# power_electronics8.net
KiCad netlist of a schematic drawn in EAGLE
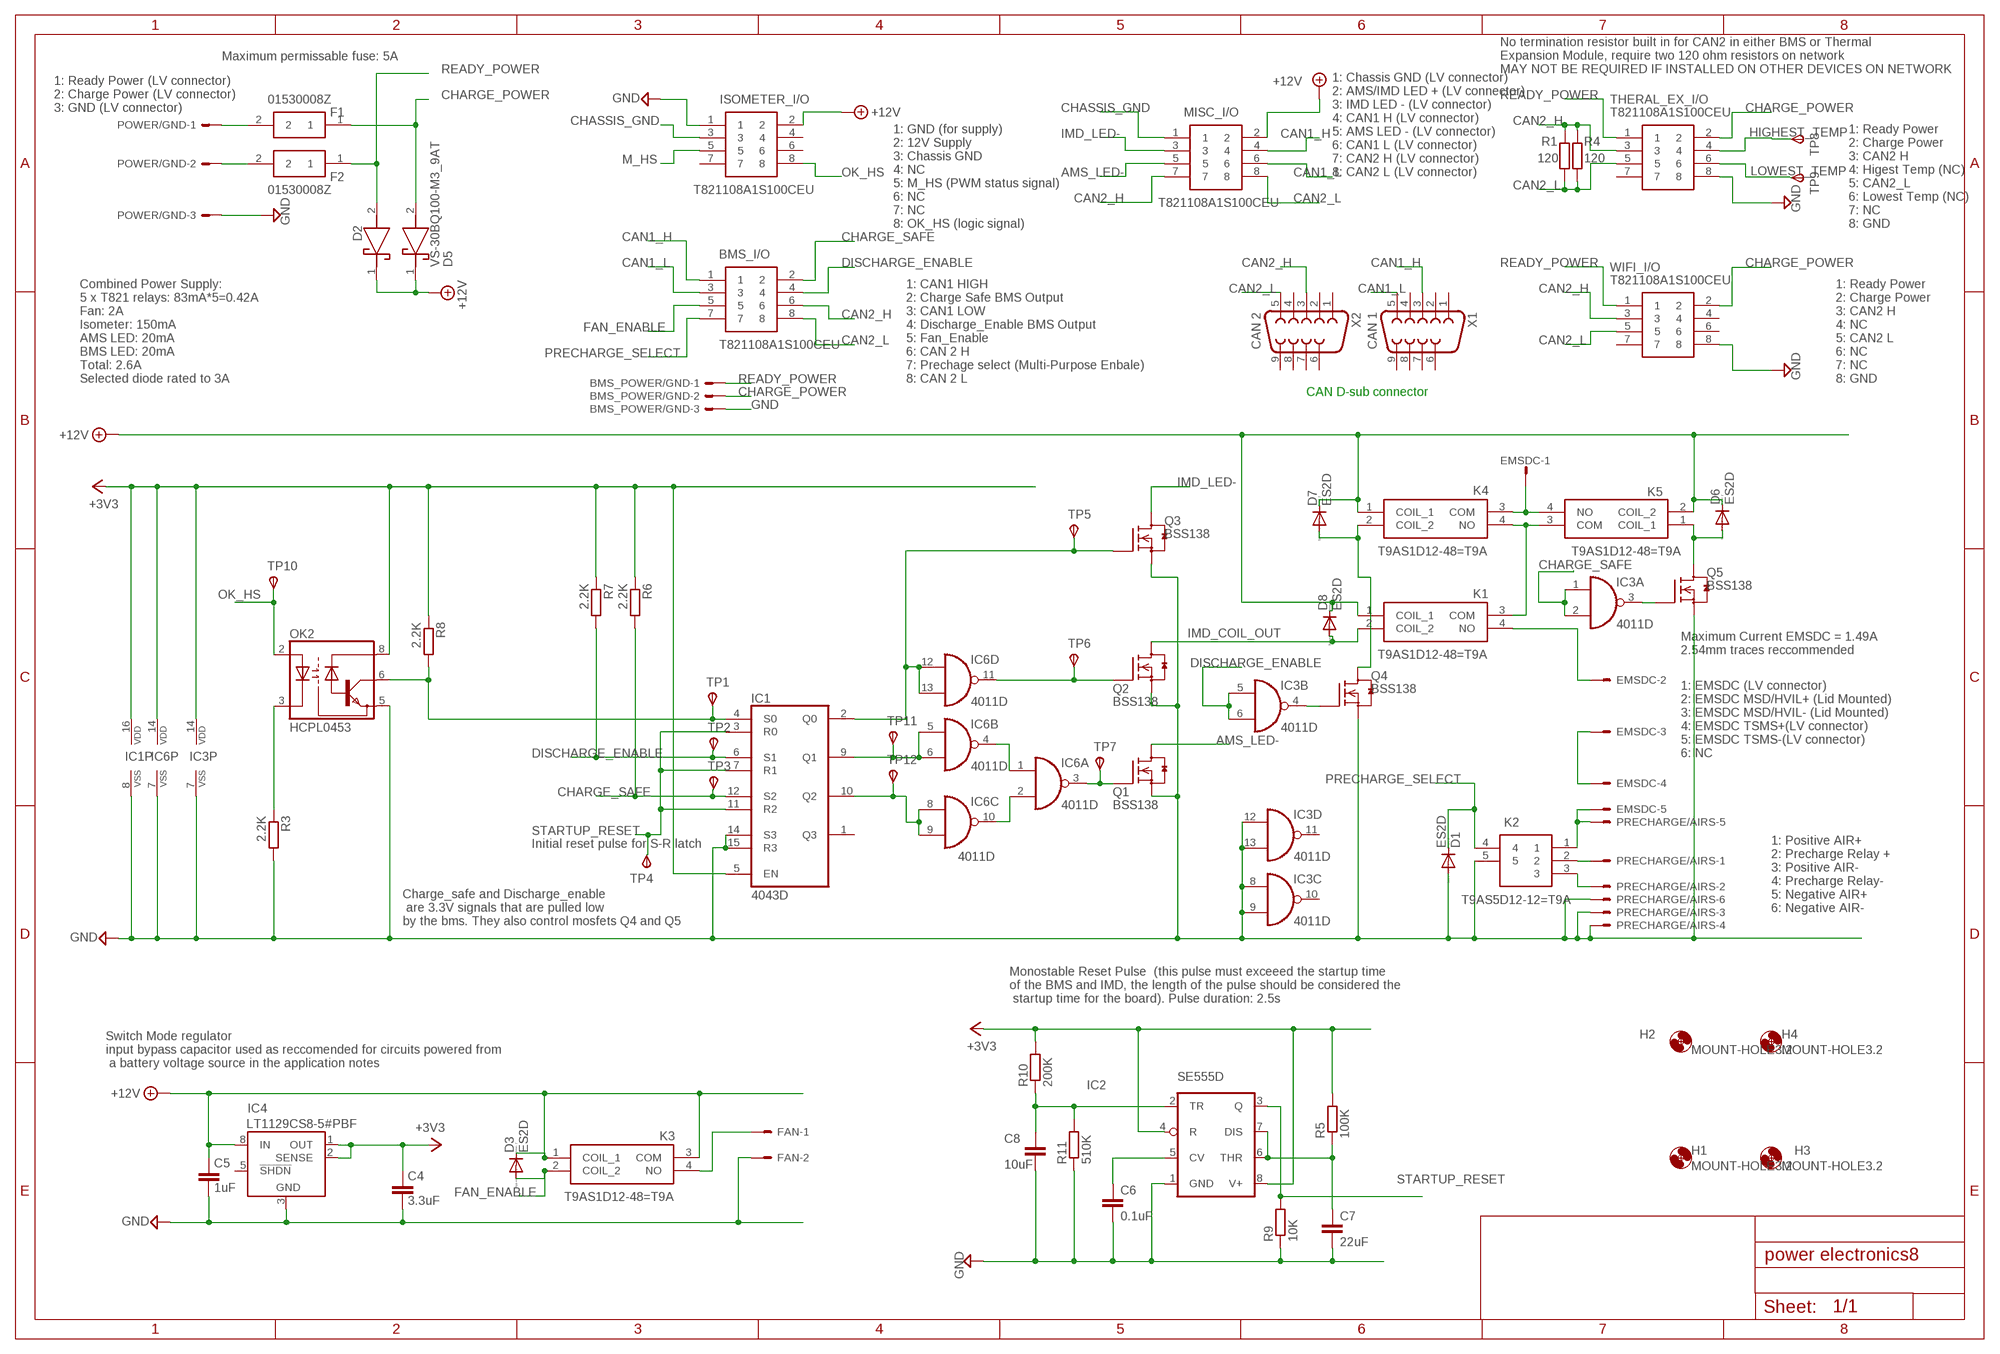
[diagram p0: schematic, sheet 1]

(export (version "E")
  (design (tool "Eeschema 10.0.6"))
  (components
    (comp (ref "BMS_I/O")
      (value "T821108A1S100CEU")
      (footprint "eagle-import:HDRV8W64P254_2X4_1778X895X915P")
      (fields (field (name "RS_PART_NUMBER") "8323569"))
      (libsource (lib "eagle-import") (part "T821108A1S100CEU"))
    )
    (comp (ref "BMS_POWER/GND")
      (value "KK-156-3")
      (footprint "eagle-import:KK-156-3")
      (fields (field (name "MF") "MOLEX"))
      (libsource (lib "eagle-import") (part "KK-156-3"))
    )
    (comp (ref "C4")
      (value "3.3uF")
      (footprint "eagle-import:C1206")
      (libsource (lib "eagle-import") (part "C-EUC1206"))
    )
    (comp (ref "C5")
      (value "1uF")
      (footprint "eagle-import:C1206")
      (libsource (lib "eagle-import") (part "C-EUC1206"))
    )
    (comp (ref "C6")
      (value "0.1uF")
      (footprint "eagle-import:C1206")
      (libsource (lib "eagle-import") (part "C-EUC1206"))
    )
    (comp (ref "C7")
      (value "22uF")
      (footprint "eagle-import:C1206")
      (libsource (lib "eagle-import") (part "C-EUC1206"))
    )
    (comp (ref "C8")
      (value "10uF")
      (footprint "eagle-import:C1206")
      (libsource (lib "eagle-import") (part "C-EUC1206"))
    )
    (comp (ref "D1")
      (value "ES2D")
      (footprint "eagle-import:SMB")
      (libsource (lib "eagle-import") (part "ES2D"))
    )
    (comp (ref "D2")
      (value "VS-30BQ100-M3_9AT")
      (footprint "eagle-import:DIOM7959X262N")
      (fields
        (field (name "MANUFACTURER_PART_NUMBER") "VS-30BQ100-M3/9AT")
        (field (name "MOUSER_PART_NUMBER") "78-VS-30BQ100-M39AT")
      )
      (libsource (lib "eagle-import") (part "VS-30BQ100-M3_9AT"))
    )
    (comp (ref "D3")
      (value "ES2D")
      (footprint "eagle-import:SMB")
      (libsource (lib "eagle-import") (part "ES2D"))
    )
    (comp (ref "D5")
      (value "VS-30BQ100-M3_9AT")
      (footprint "eagle-import:DIOM7959X262N")
      (fields
        (field (name "MANUFACTURER_PART_NUMBER") "VS-30BQ100-M3/9AT")
        (field (name "MOUSER_PART_NUMBER") "78-VS-30BQ100-M39AT")
      )
      (libsource (lib "eagle-import") (part "VS-30BQ100-M3_9AT"))
    )
    (comp (ref "D6")
      (value "ES2D")
      (footprint "eagle-import:SMB")
      (libsource (lib "eagle-import") (part "ES2D"))
    )
    (comp (ref "D7")
      (value "ES2D")
      (footprint "eagle-import:SMB")
      (libsource (lib "eagle-import") (part "ES2D"))
    )
    (comp (ref "D8")
      (value "ES2D")
      (footprint "eagle-import:SMB")
      (libsource (lib "eagle-import") (part "ES2D"))
    )
    (comp (ref "EMSDC")
      (value "KK-156-6")
      (footprint "eagle-import:KK-156-6")
      (fields (field (name "MF") "MOLEX"))
      (libsource (lib "eagle-import") (part "KK-156-6"))
    )
    (comp (ref "F1")
      (value "01530008Z")
      (footprint "eagle-import:01530008")
      (fields (field (name "RS_PART_NUMBER") "3607317"))
      (libsource (lib "eagle-import") (part "01530008Z"))
    )
    (comp (ref "F2")
      (value "01530008Z")
      (footprint "eagle-import:01530008")
      (fields (field (name "RS_PART_NUMBER") "3607317"))
      (libsource (lib "eagle-import") (part "01530008Z"))
    )
    (comp (ref "FAN")
      (value "KK-156-2")
      (footprint "eagle-import:KK-156-2")
      (fields (field (name "MF") "MOLEX"))
      (libsource (lib "eagle-import") (part "KK-156-2"))
    )
    (comp (ref "H1")
      (value "MOUNT-HOLE3.2")
      (footprint "eagle-import:3,2")
      (libsource (lib "eagle-import") (part "MOUNT-HOLE3.2"))
    )
    (comp (ref "H2")
      (value "MOUNT-HOLE3.2")
      (footprint "eagle-import:3,2")
      (libsource (lib "eagle-import") (part "MOUNT-HOLE3.2"))
    )
    (comp (ref "H3")
      (value "MOUNT-HOLE3.2")
      (footprint "eagle-import:3,2")
      (libsource (lib "eagle-import") (part "MOUNT-HOLE3.2"))
    )
    (comp (ref "H4")
      (value "MOUNT-HOLE3.2")
      (footprint "eagle-import:3,2")
      (libsource (lib "eagle-import") (part "MOUNT-HOLE3.2"))
    )
    (comp (ref "IC1")
      (value "4043D")
      (footprint "eagle-import:SO16")
      (libsource (lib "eagle-import") (part "4043D"))
    )
    (comp (ref "IC2")
      (value "SE555D")
      (footprint "eagle-import:SO08")
      (libsource (lib "eagle-import") (part "555DSE"))
    )
    (comp (ref "IC3")
      (value "4011D")
      (footprint "eagle-import:SO14")
      (libsource (lib "eagle-import") (part "4011D"))
    )
    (comp (ref "IC4")
      (value "LT1129CS8")
      (footprint "eagle-import:SOIC8")
      (fields (field (name "MPN") "LT1129CS8-5#PBF"))
      (libsource (lib "eagle-import") (part "LT1129CS8"))
    )
    (comp (ref "IC6")
      (value "4011D")
      (footprint "eagle-import:SO14")
      (libsource (lib "eagle-import") (part "4011D"))
    )
    (comp (ref "ISOMETER_I/O")
      (value "T821108A1S100CEU")
      (footprint "eagle-import:HDRV8W64P254_2X4_1778X895X915P")
      (fields (field (name "RS_PART_NUMBER") "8323569"))
      (libsource (lib "eagle-import") (part "T821108A1S100CEU"))
    )
    (comp (ref "K1")
      (value "T9AS1D12-48=T9A")
      (footprint "eagle-import:T9AS1D1248T9A")
      (fields (field (name "RS_PART_NUMBER") "6802534P"))
      (libsource (lib "eagle-import") (part "T9AS1D12-48=T9A"))
    )
    (comp (ref "K2")
      (value "T9AS5D12-12=T9A")
      (footprint "eagle-import:T9AS1D12")
      (fields (field (name "RS_PART_NUMBER") "6802528"))
      (libsource (lib "eagle-import") (part "T9AS5D12-12=T9A"))
    )
    (comp (ref "K3")
      (value "T9AS1D12-48=T9A")
      (footprint "eagle-import:T9AS1D1248T9A")
      (fields (field (name "RS_PART_NUMBER") "6802534P"))
      (libsource (lib "eagle-import") (part "T9AS1D12-48=T9A"))
    )
    (comp (ref "K4")
      (value "T9AS1D12-48=T9A")
      (footprint "eagle-import:T9AS1D1248T9A")
      (fields (field (name "RS_PART_NUMBER") "6802534P"))
      (libsource (lib "eagle-import") (part "T9AS1D12-48=T9A"))
    )
    (comp (ref "K5")
      (value "T9AS1D12-48=T9A")
      (footprint "eagle-import:T9AS1D1248T9A")
      (fields (field (name "RS_PART_NUMBER") "6802534P"))
      (libsource (lib "eagle-import") (part "T9AS1D12-48=T9A"))
    )
    (comp (ref "MISC_I/O")
      (value "T821108A1S100CEU")
      (footprint "eagle-import:HDRV8W64P254_2X4_1778X895X915P")
      (fields (field (name "RS_PART_NUMBER") "8323569"))
      (libsource (lib "eagle-import") (part "T821108A1S100CEU"))
    )
    (comp (ref "OK2")
      (value "HCPL0453")
      (footprint "eagle-import:SOIC08")
      (fields (field (name "MF") "AGILENT TECHNOLOGIES") (field (name "MPN") "HCPL-0453-000E"))
      (libsource (lib "eagle-import") (part "HCPL0453"))
    )
    (comp (ref "POWER/GND")
      (value "KK-156-3")
      (footprint "eagle-import:KK-156-3")
      (fields (field (name "MF") "MOLEX"))
      (libsource (lib "eagle-import") (part "KK-156-3"))
    )
    (comp (ref "PRECHARGE/AIRS")
      (value "KK-156-6")
      (footprint "eagle-import:KK-156-6")
      (fields (field (name "MF") "MOLEX"))
      (libsource (lib "eagle-import") (part "KK-156-6"))
    )
    (comp (ref "Q1")
      (value "BSS138")
      (footprint "eagle-import:SOT23")
      (libsource (lib "eagle-import") (part "BSS138"))
    )
    (comp (ref "Q2")
      (value "BSS138")
      (footprint "eagle-import:SOT23")
      (libsource (lib "eagle-import") (part "BSS138"))
    )
    (comp (ref "Q3")
      (value "BSS138")
      (footprint "eagle-import:SOT23")
      (libsource (lib "eagle-import") (part "BSS138"))
    )
    (comp (ref "Q4")
      (value "BSS138")
      (footprint "eagle-import:SOT23")
      (libsource (lib "eagle-import") (part "BSS138"))
    )
    (comp (ref "Q5")
      (value "BSS138")
      (footprint "eagle-import:SOT23")
      (libsource (lib "eagle-import") (part "BSS138"))
    )
    (comp (ref "R1")
      (value "120")
      (footprint "eagle-import:R1206")
      (libsource (lib "eagle-import") (part "R-EU_R1206"))
    )
    (comp (ref "R3")
      (value "2.2K")
      (footprint "eagle-import:R1206")
      (libsource (lib "eagle-import") (part "R-EU_R1206"))
    )
    (comp (ref "R4")
      (value "120")
      (footprint "eagle-import:R1206")
      (libsource (lib "eagle-import") (part "R-EU_R1206"))
    )
    (comp (ref "R5")
      (value "100K")
      (footprint "eagle-import:R1206")
      (libsource (lib "eagle-import") (part "R-EU_R1206"))
    )
    (comp (ref "R6")
      (value "2.2K")
      (footprint "eagle-import:R1206")
      (libsource (lib "eagle-import") (part "R-EU_R1206"))
    )
    (comp (ref "R7")
      (value "2.2K")
      (footprint "eagle-import:R1206")
      (libsource (lib "eagle-import") (part "R-EU_R1206"))
    )
    (comp (ref "R8")
      (value "2.2K")
      (footprint "eagle-import:R1206")
      (libsource (lib "eagle-import") (part "R-EU_R1206"))
    )
    (comp (ref "R9")
      (value "10K")
      (footprint "eagle-import:R1206")
      (libsource (lib "eagle-import") (part "R-EU_R1206"))
    )
    (comp (ref "R10")
      (value "200K")
      (footprint "eagle-import:R1206")
      (libsource (lib "eagle-import") (part "R-EU_R1206"))
    )
    (comp (ref "R11")
      (value "510K")
      (footprint "eagle-import:R1206")
      (libsource (lib "eagle-import") (part "R-EU_R1206"))
    )
    (comp (ref "THERAL_EX_I/O")
      (value "T821108A1S100CEU")
      (footprint "eagle-import:HDRV8W64P254_2X4_1778X895X915P")
      (fields (field (name "RS_PART_NUMBER") "8323569"))
      (libsource (lib "eagle-import") (part "T821108A1S100CEU"))
    )
    (comp (ref "TP1")
      (value "TPSTP11R")
      (footprint "eagle-import:TP11R")
      (libsource (lib "eagle-import") (part "TPSTP11R"))
    )
    (comp (ref "TP2")
      (value "TPSTP11R")
      (footprint "eagle-import:TP11R")
      (libsource (lib "eagle-import") (part "TPSTP11R"))
    )
    (comp (ref "TP3")
      (value "TPSTP11R")
      (footprint "eagle-import:TP11R")
      (libsource (lib "eagle-import") (part "TPSTP11R"))
    )
    (comp (ref "TP4")
      (value "TPSTP11R")
      (footprint "eagle-import:TP11R")
      (libsource (lib "eagle-import") (part "TPSTP11R"))
    )
    (comp (ref "TP5")
      (value "TPSTP11R")
      (footprint "eagle-import:TP11R")
      (libsource (lib "eagle-import") (part "TPSTP11R"))
    )
    (comp (ref "TP6")
      (value "TPSTP11R")
      (footprint "eagle-import:TP11R")
      (libsource (lib "eagle-import") (part "TPSTP11R"))
    )
    (comp (ref "TP7")
      (value "TPSTP11R")
      (footprint "eagle-import:TP11R")
      (libsource (lib "eagle-import") (part "TPSTP11R"))
    )
    (comp (ref "TP8")
      (value "TPSTP11R")
      (footprint "eagle-import:TP11R")
      (libsource (lib "eagle-import") (part "TPSTP11R"))
    )
    (comp (ref "TP9")
      (value "TPSTP11R")
      (footprint "eagle-import:TP11R")
      (libsource (lib "eagle-import") (part "TPSTP11R"))
    )
    (comp (ref "TP10")
      (value "TPSTP11R")
      (footprint "eagle-import:TP11R")
      (libsource (lib "eagle-import") (part "TPSTP11R"))
    )
    (comp (ref "TP11")
      (value "TPSTP11R")
      (footprint "eagle-import:TP11R")
      (libsource (lib "eagle-import") (part "TPSTP11R"))
    )
    (comp (ref "TP12")
      (value "TPSTP11R")
      (footprint "eagle-import:TP11R")
      (libsource (lib "eagle-import") (part "TPSTP11R"))
    )
    (comp (ref "WIFI_I/O")
      (value "T821108A1S100CEU")
      (footprint "eagle-import:HDRV8W64P254_2X4_1778X895X915P")
      (fields (field (name "RS_PART_NUMBER") "8323569"))
      (libsource (lib "eagle-import") (part "T821108A1S100CEU"))
    )
    (comp (ref "X1")
      (value "CAN 1")
      (footprint "eagle-import:F09V")
      (libsource (lib "eagle-import") (part "F09V"))
    )
    (comp (ref "X2")
      (value "CAN 2")
      (footprint "eagle-import:F09V")
      (libsource (lib "eagle-import") (part "F09V"))
    )
  )
  (nets
    (net (code "1") (name "+3V3") (class "Default")
      (node (ref "C4") (pin "1") (pinfunction "1_1") (pintype "passive"))
      (node (ref "IC1") (pin "16") (pinfunction "VDD_16") (pintype "power_in"))
      (node (ref "IC1") (pin "5") (pinfunction "EN_5") (pintype "input"))
      (node (ref "IC2") (pin "4") (pinfunction "R_4") (pintype "input"))
      (node (ref "IC2") (pin "8") (pinfunction "V+_8") (pintype "power_in"))
      (node (ref "IC3") (pin "14") (pinfunction "VDD_14") (pintype "power_in"))
      (node (ref "IC4") (pin "1") (pinfunction "OUT_1") (pintype "output"))
      (node (ref "IC4") (pin "2") (pinfunction "SENSE_2") (pintype "input"))
      (node (ref "IC6") (pin "14") (pinfunction "VDD_14") (pintype "power_in"))
      (node (ref "OK2") (pin "8") (pinfunction "VCC_8") (pintype "passive"))
      (node (ref "R10") (pin "2") (pinfunction "2_2") (pintype "passive"))
      (node (ref "R5") (pin "2") (pinfunction "2_2") (pintype "passive"))
      (node (ref "R6") (pin "1") (pinfunction "1_1") (pintype "passive"))
      (node (ref "R7") (pin "1") (pinfunction "1_1") (pintype "passive"))
      (node (ref "R8") (pin "1") (pinfunction "1_1") (pintype "passive"))
    )
    (net (code "2") (name "+12V") (class "Default")
      (node (ref "C5") (pin "1") (pinfunction "1_1") (pintype "passive"))
      (node (ref "D2") (pin "1") (pinfunction "K_1") (pintype "bidirectional"))
      (node (ref "D3") (pin "C") (pinfunction "C_C") (pintype "passive"))
      (node (ref "D5") (pin "1") (pinfunction "K_1") (pintype "bidirectional"))
      (node (ref "D6") (pin "C") (pinfunction "C_C") (pintype "passive"))
      (node (ref "D7") (pin "C") (pinfunction "C_C") (pintype "passive"))
      (node (ref "D8") (pin "C") (pinfunction "C_C") (pintype "passive"))
      (node (ref "IC4") (pin "8") (pinfunction "IN_8") (pintype "input"))
      (node (ref "ISOMETER_I/O") (pin "2") (pinfunction "2_2") (pintype "bidirectional"))
      (node (ref "K1") (pin "1") (pinfunction "COIL_1_1") (pintype "bidirectional"))
      (node (ref "K3") (pin "1") (pinfunction "COIL_1_1") (pintype "bidirectional"))
      (node (ref "K3") (pin "3") (pinfunction "COM_3") (pintype "bidirectional"))
      (node (ref "K4") (pin "1") (pinfunction "COIL_1_1") (pintype "bidirectional"))
      (node (ref "K5") (pin "2") (pinfunction "COIL_2_2") (pintype "bidirectional"))
      (node (ref "MISC_I/O") (pin "2") (pinfunction "2_2") (pintype "bidirectional"))
    )
    (net (code "3") (name "/AMS_LED-") (class "Default")
      (node (ref "MISC_I/O") (pin "5") (pinfunction "5_5") (pintype "bidirectional"))
      (node (ref "Q1") (pin "3") (pinfunction "D_3") (pintype "passive"))
    )
    (net (code "4") (name "/CAN1_H") (class "Default")
      (node (ref "BMS_I/O") (pin "1") (pinfunction "1_1") (pintype "bidirectional"))
      (node (ref "MISC_I/O") (pin "4") (pinfunction "4_4") (pintype "bidirectional"))
      (node (ref "X1") (pin "3") (pinfunction "3_3") (pintype "passive"))
    )
    (net (code "5") (name "/CAN1_L") (class "Default")
      (node (ref "BMS_I/O") (pin "3") (pinfunction "3_3") (pintype "bidirectional"))
      (node (ref "MISC_I/O") (pin "6") (pinfunction "6_6") (pintype "bidirectional"))
      (node (ref "X1") (pin "5") (pinfunction "5_5") (pintype "passive"))
    )
    (net (code "6") (name "/CAN2_H") (class "Default")
      (node (ref "BMS_I/O") (pin "6") (pinfunction "6_6") (pintype "bidirectional"))
      (node (ref "MISC_I/O") (pin "7") (pinfunction "7_7") (pintype "bidirectional"))
      (node (ref "R1") (pin "1") (pinfunction "1_1") (pintype "passive"))
      (node (ref "R4") (pin "1") (pinfunction "1_1") (pintype "passive"))
      (node (ref "THERAL_EX_I/O") (pin "3") (pinfunction "3_3") (pintype "bidirectional"))
      (node (ref "WIFI_I/O") (pin "3") (pinfunction "3_3") (pintype "bidirectional"))
      (node (ref "X2") (pin "3") (pinfunction "3_3") (pintype "passive"))
    )
    (net (code "7") (name "/CAN2_L") (class "Default")
      (node (ref "BMS_I/O") (pin "8") (pinfunction "8_8") (pintype "bidirectional"))
      (node (ref "MISC_I/O") (pin "8") (pinfunction "8_8") (pintype "bidirectional"))
      (node (ref "R1") (pin "2") (pinfunction "2_2") (pintype "passive"))
      (node (ref "R4") (pin "2") (pinfunction "2_2") (pintype "passive"))
      (node (ref "THERAL_EX_I/O") (pin "5") (pinfunction "5_5") (pintype "bidirectional"))
      (node (ref "WIFI_I/O") (pin "5") (pinfunction "5_5") (pintype "bidirectional"))
      (node (ref "X2") (pin "5") (pinfunction "5_5") (pintype "passive"))
    )
    (net (code "8") (name "/CHARGE_POWER") (class "Default")
      (node (ref "BMS_POWER/GND") (pin "2") (pinfunction "S_2") (pintype "passive"))
      (node (ref "D5") (pin "2") (pinfunction "A_2") (pintype "bidirectional"))
      (node (ref "F1") (pin "1") (pinfunction "1_1") (pintype "bidirectional"))
      (node (ref "THERAL_EX_I/O") (pin "2") (pinfunction "2_2") (pintype "bidirectional"))
      (node (ref "WIFI_I/O") (pin "2") (pinfunction "2_2") (pintype "bidirectional"))
    )
    (net (code "9") (name "/CHARGE_SAFE") (class "Default")
      (node (ref "BMS_I/O") (pin "2") (pinfunction "2_2") (pintype "bidirectional"))
      (node (ref "IC1") (pin "12") (pinfunction "S2_12") (pintype "input"))
      (node (ref "IC3") (pin "1") (pinfunction "I0_1") (pintype "input"))
      (node (ref "IC3") (pin "2") (pinfunction "I1_2") (pintype "input"))
      (node (ref "R6") (pin "2") (pinfunction "2_2") (pintype "passive"))
      (node (ref "TP3") (pin "TP") (pinfunction "PP_TP") (pintype "input"))
    )
    (net (code "10") (name "/CHASSIS_GND") (class "Default")
      (node (ref "ISOMETER_I/O") (pin "3") (pinfunction "3_3") (pintype "bidirectional"))
      (node (ref "MISC_I/O") (pin "1") (pinfunction "1_1") (pintype "bidirectional"))
    )
    (net (code "11") (name "/DISCHARGE_ENABLE") (class "Default")
      (node (ref "BMS_I/O") (pin "4") (pinfunction "4_4") (pintype "bidirectional"))
      (node (ref "IC1") (pin "6") (pinfunction "S1_6") (pintype "input"))
      (node (ref "IC3") (pin "5") (pinfunction "I0_5") (pintype "input"))
      (node (ref "IC3") (pin "6") (pinfunction "I1_6") (pintype "input"))
      (node (ref "R7") (pin "2") (pinfunction "2_2") (pintype "passive"))
      (node (ref "TP2") (pin "TP") (pinfunction "PP_TP") (pintype "input"))
    )
    (net (code "12") (name "/FAN_ENABLE") (class "Default")
      (node (ref "BMS_I/O") (pin "5") (pinfunction "5_5") (pintype "bidirectional"))
      (node (ref "D3") (pin "A") (pinfunction "A_A") (pintype "passive"))
      (node (ref "K3") (pin "2") (pinfunction "COIL_2_2") (pintype "bidirectional"))
    )
    (net (code "13") (name "/HIGHEST_TEMP") (class "Default")
      (node (ref "THERAL_EX_I/O") (pin "4") (pinfunction "4_4") (pintype "bidirectional"))
      (node (ref "TP8") (pin "TP") (pinfunction "PP_TP") (pintype "input"))
    )
    (net (code "14") (name "/IMD_COIL_OUT") (class "Default")
      (node (ref "D8") (pin "A") (pinfunction "A_A") (pintype "passive"))
      (node (ref "K1") (pin "2") (pinfunction "COIL_2_2") (pintype "bidirectional"))
      (node (ref "Q2") (pin "3") (pinfunction "D_3") (pintype "passive"))
    )
    (net (code "15") (name "/IMD_LED-") (class "Default")
      (node (ref "MISC_I/O") (pin "3") (pinfunction "3_3") (pintype "bidirectional"))
      (node (ref "Q3") (pin "3") (pinfunction "D_3") (pintype "passive"))
    )
    (net (code "16") (name "/LOWEST_TEMP") (class "Default")
      (node (ref "THERAL_EX_I/O") (pin "6") (pinfunction "6_6") (pintype "bidirectional"))
      (node (ref "TP9") (pin "TP") (pinfunction "PP_TP") (pintype "input"))
    )
    (net (code "17") (name "/M_HS") (class "Default")
      (node (ref "ISOMETER_I/O") (pin "5") (pinfunction "5_5") (pintype "bidirectional"))
    )
    (net (code "18") (name "/OK_HS") (class "Default")
      (node (ref "ISOMETER_I/O") (pin "8") (pinfunction "8_8") (pintype "bidirectional"))
      (node (ref "OK2") (pin "2") (pinfunction "A_2") (pintype "passive"))
      (node (ref "TP10") (pin "TP") (pinfunction "PP_TP") (pintype "input"))
    )
    (net (code "19") (name "/PRECHARGE_SELECT") (class "Default")
      (node (ref "BMS_I/O") (pin "7") (pinfunction "7_7") (pintype "bidirectional"))
      (node (ref "D1") (pin "C") (pinfunction "C_C") (pintype "passive"))
      (node (ref "K2") (pin "4") (pinfunction "4_4") (pintype "bidirectional"))
    )
    (net (code "20") (name "/READY_POWER") (class "Default")
      (node (ref "BMS_POWER/GND") (pin "1") (pinfunction "S_1") (pintype "passive"))
      (node (ref "D2") (pin "2") (pinfunction "A_2") (pintype "bidirectional"))
      (node (ref "F2") (pin "1") (pinfunction "1_1") (pintype "bidirectional"))
      (node (ref "THERAL_EX_I/O") (pin "1") (pinfunction "1_1") (pintype "bidirectional"))
      (node (ref "WIFI_I/O") (pin "1") (pinfunction "1_1") (pintype "bidirectional"))
    )
    (net (code "21") (name "/STARTUP_RESET") (class "Default")
      (node (ref "IC1") (pin "11") (pinfunction "R2_11") (pintype "input"))
      (node (ref "IC1") (pin "3") (pinfunction "R0_3") (pintype "input"))
      (node (ref "IC1") (pin "7") (pinfunction "R1_7") (pintype "input"))
      (node (ref "IC2") (pin "3") (pinfunction "Q_3") (pintype "output"))
      (node (ref "R9") (pin "2") (pinfunction "2_2") (pintype "passive"))
      (node (ref "TP4") (pin "TP") (pinfunction "PP_TP") (pintype "input"))
    )
    (net (code "22") (name "GND") (class "Default")
      (node (ref "BMS_POWER/GND") (pin "3") (pinfunction "S_3") (pintype "passive"))
      (node (ref "C4") (pin "2") (pinfunction "2_2") (pintype "passive"))
      (node (ref "C5") (pin "2") (pinfunction "2_2") (pintype "passive"))
      (node (ref "C6") (pin "2") (pinfunction "2_2") (pintype "passive"))
      (node (ref "C7") (pin "2") (pinfunction "2_2") (pintype "passive"))
      (node (ref "C8") (pin "2") (pinfunction "2_2") (pintype "passive"))
      (node (ref "D1") (pin "A") (pinfunction "A_A") (pintype "passive"))
      (node (ref "FAN") (pin "2") (pinfunction "S_2") (pintype "passive"))
      (node (ref "IC1") (pin "14") (pinfunction "S3_14") (pintype "input"))
      (node (ref "IC1") (pin "15") (pinfunction "R3_15") (pintype "input"))
      (node (ref "IC1") (pin "8") (pinfunction "VSS_8") (pintype "power_in"))
      (node (ref "IC2") (pin "1") (pinfunction "GND_1") (pintype "power_in"))
      (node (ref "IC3") (pin "12") (pinfunction "I0_12") (pintype "input"))
      (node (ref "IC3") (pin "13") (pinfunction "I1_13") (pintype "input"))
      (node (ref "IC3") (pin "7") (pinfunction "VSS_7") (pintype "power_in"))
      (node (ref "IC3") (pin "8") (pinfunction "I0_8") (pintype "input"))
      (node (ref "IC3") (pin "9") (pinfunction "I1_9") (pintype "input"))
      (node (ref "IC4") (pin "3") (pinfunction "GND_3") (pintype "power_in"))
      (node (ref "IC6") (pin "7") (pinfunction "VSS_7") (pintype "power_in"))
      (node (ref "ISOMETER_I/O") (pin "1") (pinfunction "1_1") (pintype "bidirectional"))
      (node (ref "K2") (pin "5") (pinfunction "5_5") (pintype "bidirectional"))
      (node (ref "OK2") (pin "5") (pinfunction "GND_5") (pintype "passive"))
      (node (ref "POWER/GND") (pin "3") (pinfunction "S_3") (pintype "passive"))
      (node (ref "PRECHARGE/AIRS") (pin "3") (pinfunction "S_3") (pintype "passive"))
      (node (ref "PRECHARGE/AIRS") (pin "4") (pinfunction "S_4") (pintype "passive"))
      (node (ref "PRECHARGE/AIRS") (pin "6") (pinfunction "S_6") (pintype "passive"))
      (node (ref "Q1") (pin "2") (pinfunction "S_2") (pintype "passive"))
      (node (ref "Q2") (pin "2") (pinfunction "S_2") (pintype "passive"))
      (node (ref "Q3") (pin "2") (pinfunction "S_2") (pintype "passive"))
      (node (ref "Q4") (pin "2") (pinfunction "S_2") (pintype "passive"))
      (node (ref "Q5") (pin "2") (pinfunction "S_2") (pintype "passive"))
      (node (ref "R11") (pin "1") (pinfunction "1_1") (pintype "passive"))
      (node (ref "R3") (pin "2") (pinfunction "2_2") (pintype "passive"))
      (node (ref "R9") (pin "1") (pinfunction "1_1") (pintype "passive"))
      (node (ref "THERAL_EX_I/O") (pin "8") (pinfunction "8_8") (pintype "bidirectional"))
      (node (ref "WIFI_I/O") (pin "8") (pinfunction "8_8") (pintype "bidirectional"))
    )
    (net (code "23") (name "Net-(EMSDCA-S)") (class "Default")
      (node (ref "EMSDC") (pin "1") (pinfunction "S_1") (pintype "passive"))
      (node (ref "K4") (pin "3") (pinfunction "COM_3") (pintype "bidirectional"))
      (node (ref "K5") (pin "4") (pinfunction "NO_4") (pintype "bidirectional"))
    )
    (net (code "24") (name "Net-(EMSDCB-S)") (class "Default")
      (node (ref "EMSDC") (pin "2") (pinfunction "S_2") (pintype "passive"))
      (node (ref "K1") (pin "4") (pinfunction "NO_4") (pintype "bidirectional"))
    )
    (net (code "25") (name "Net-(EMSDCC-S)") (class "Default")
      (node (ref "EMSDC") (pin "3") (pinfunction "S_3") (pintype "passive"))
      (node (ref "EMSDC") (pin "4") (pinfunction "S_4") (pintype "passive"))
    )
    (net (code "26") (name "Net-(EMSDCE-S)") (class "Default")
      (node (ref "EMSDC") (pin "5") (pinfunction "S_5") (pintype "passive"))
      (node (ref "K2") (pin "1") (pinfunction "1_1") (pintype "bidirectional"))
      (node (ref "PRECHARGE/AIRS") (pin "5") (pinfunction "S_5") (pintype "passive"))
    )
    (net (code "27") (name "Net-(FANA-S)") (class "Default")
      (node (ref "FAN") (pin "1") (pinfunction "S_1") (pintype "passive"))
      (node (ref "K3") (pin "4") (pinfunction "NO_4") (pintype "bidirectional"))
    )
    (net (code "28") (name "Net-(IC1A-Q0)") (class "Default")
      (node (ref "IC1") (pin "2") (pinfunction "Q0_2") (pintype "output"))
      (node (ref "IC6") (pin "12") (pinfunction "I0_12") (pintype "input"))
      (node (ref "IC6") (pin "13") (pinfunction "I1_13") (pintype "input"))
      (node (ref "Q3") (pin "1") (pinfunction "G_1") (pintype "passive"))
      (node (ref "TP5") (pin "TP") (pinfunction "PP_TP") (pintype "input"))
    )
    (net (code "29") (name "Net-(IC1A-Q1)") (class "Default")
      (node (ref "IC1") (pin "9") (pinfunction "Q1_9") (pintype "output"))
      (node (ref "IC6") (pin "5") (pinfunction "I0_5") (pintype "input"))
      (node (ref "IC6") (pin "6") (pinfunction "I1_6") (pintype "input"))
      (node (ref "TP11") (pin "TP") (pinfunction "PP_TP") (pintype "input"))
    )
    (net (code "30") (name "Net-(IC1A-Q2)") (class "Default")
      (node (ref "IC1") (pin "10") (pinfunction "Q2_10") (pintype "output"))
      (node (ref "IC6") (pin "8") (pinfunction "I0_8") (pintype "input"))
      (node (ref "IC6") (pin "9") (pinfunction "I1_9") (pintype "input"))
      (node (ref "TP12") (pin "TP") (pinfunction "PP_TP") (pintype "input"))
    )
    (net (code "31") (name "Net-(IC1A-S0)") (class "Default")
      (node (ref "IC1") (pin "4") (pinfunction "S0_4") (pintype "input"))
      (node (ref "OK2") (pin "6") (pinfunction "VO_6") (pintype "passive"))
      (node (ref "R8") (pin "2") (pinfunction "2_2") (pintype "passive"))
      (node (ref "TP1") (pin "TP") (pinfunction "PP_TP") (pintype "input"))
    )
    (net (code "32") (name "Net-(IC2-CV)") (class "Default")
      (node (ref "C6") (pin "1") (pinfunction "1_1") (pintype "passive"))
      (node (ref "IC2") (pin "5") (pinfunction "CV_5") (pintype "input"))
    )
    (net (code "33") (name "Net-(IC2-DIS)") (class "Default")
      (node (ref "C7") (pin "1") (pinfunction "1_1") (pintype "passive"))
      (node (ref "IC2") (pin "6") (pinfunction "THR_6") (pintype "input"))
      (node (ref "IC2") (pin "7") (pinfunction "DIS_7") (pintype "input"))
      (node (ref "R5") (pin "1") (pinfunction "1_1") (pintype "passive"))
    )
    (net (code "34") (name "Net-(IC2-TR)") (class "Default")
      (node (ref "C8") (pin "1") (pinfunction "1_1") (pintype "passive"))
      (node (ref "IC2") (pin "2") (pinfunction "TR_2") (pintype "input"))
      (node (ref "R10") (pin "1") (pinfunction "1_1") (pintype "passive"))
      (node (ref "R11") (pin "2") (pinfunction "2_2") (pintype "passive"))
    )
    (net (code "35") (name "Net-(IC3A-O)") (class "Default")
      (node (ref "IC3") (pin "3") (pinfunction "O_3") (pintype "output"))
      (node (ref "Q5") (pin "1") (pinfunction "G_1") (pintype "passive"))
    )
    (net (code "36") (name "Net-(IC3B-O)") (class "Default")
      (node (ref "IC3") (pin "4") (pinfunction "O_4") (pintype "output"))
      (node (ref "Q4") (pin "1") (pinfunction "G_1") (pintype "passive"))
    )
    (net (code "37") (name "Net-(IC6A-I0)") (class "Default")
      (node (ref "IC6") (pin "1") (pinfunction "I0_1") (pintype "input"))
      (node (ref "IC6") (pin "4") (pinfunction "O_4") (pintype "output"))
    )
    (net (code "38") (name "Net-(IC6A-I1)") (class "Default")
      (node (ref "IC6") (pin "10") (pinfunction "O_10") (pintype "output"))
      (node (ref "IC6") (pin "2") (pinfunction "I1_2") (pintype "input"))
    )
    (net (code "39") (name "Net-(IC6A-O)") (class "Default")
      (node (ref "IC6") (pin "3") (pinfunction "O_3") (pintype "output"))
      (node (ref "Q1") (pin "1") (pinfunction "G_1") (pintype "passive"))
      (node (ref "TP7") (pin "TP") (pinfunction "PP_TP") (pintype "input"))
    )
    (net (code "40") (name "Net-(IC6D-O)") (class "Default")
      (node (ref "IC6") (pin "11") (pinfunction "O_11") (pintype "output"))
      (node (ref "Q2") (pin "1") (pinfunction "G_1") (pintype "passive"))
      (node (ref "TP6") (pin "TP") (pinfunction "PP_TP") (pintype "input"))
    )
    (net (code "41") (name "Net-(K1-COM)") (class "Default")
      (node (ref "K1") (pin "3") (pinfunction "COM_3") (pintype "bidirectional"))
      (node (ref "K4") (pin "4") (pinfunction "NO_4") (pintype "bidirectional"))
      (node (ref "K5") (pin "3") (pinfunction "COM_3") (pintype "bidirectional"))
    )
    (net (code "42") (name "Net-(K4-COIL_2)") (class "Default")
      (node (ref "D7") (pin "A") (pinfunction "A_A") (pintype "passive"))
      (node (ref "K4") (pin "2") (pinfunction "COIL_2_2") (pintype "bidirectional"))
      (node (ref "Q4") (pin "3") (pinfunction "D_3") (pintype "passive"))
    )
    (net (code "43") (name "Net-(K5-COIL_1)") (class "Default")
      (node (ref "D6") (pin "A") (pinfunction "A_A") (pintype "passive"))
      (node (ref "K5") (pin "1") (pinfunction "COIL_1_1") (pintype "bidirectional"))
      (node (ref "Q5") (pin "3") (pinfunction "D_3") (pintype "passive"))
    )
    (net (code "44") (name "Net-(OK2-C)") (class "Default")
      (node (ref "OK2") (pin "3") (pinfunction "C_3") (pintype "passive"))
      (node (ref "R3") (pin "1") (pinfunction "1_1") (pintype "passive"))
    )
    (net (code "45") (name "Net-(POWER/GNDA-S)") (class "Default")
      (node (ref "F1") (pin "2") (pinfunction "2_2") (pintype "bidirectional"))
      (node (ref "POWER/GND") (pin "1") (pinfunction "S_1") (pintype "passive"))
    )
    (net (code "46") (name "Net-(POWER/GNDB-S)") (class "Default")
      (node (ref "F2") (pin "2") (pinfunction "2_2") (pintype "bidirectional"))
      (node (ref "POWER/GND") (pin "2") (pinfunction "S_2") (pintype "passive"))
    )
    (net (code "47") (name "Net-(PRECHARGE/AIRSA-S)") (class "Default")
      (node (ref "K2") (pin "2") (pinfunction "2_2") (pintype "bidirectional"))
      (node (ref "PRECHARGE/AIRS") (pin "1") (pinfunction "S_1") (pintype "passive"))
    )
    (net (code "48") (name "Net-(PRECHARGE/AIRSB-S)") (class "Default")
      (node (ref "K2") (pin "3") (pinfunction "3_3") (pintype "bidirectional"))
      (node (ref "PRECHARGE/AIRS") (pin "2") (pinfunction "S_2") (pintype "passive"))
    )
    (net (code "49") (name "unconnected-(IC1A-Q3-Pad1)") (class "Default")
      (node (ref "IC1") (pin "1") (pinfunction "Q3_1") (pintype "output"))
    )
    (net (code "50") (name "unconnected-(IC3C-O-Pad10)") (class "Default")
      (node (ref "IC3") (pin "10") (pinfunction "O_10") (pintype "output"))
    )
    (net (code "51") (name "unconnected-(IC3D-O-Pad11)") (class "Default")
      (node (ref "IC3") (pin "11") (pinfunction "O_11") (pintype "output"))
    )
    (net (code "52") (name "unconnected-(IC4A-~{SHDN}-Pad5)") (class "Default")
      (node (ref "IC4") (pin "5") (pinfunction "~{SHDN}_5") (pintype "input"))
    )
    (net (code "53") (name "unconnected-(ISOMETER_I/O-Pad4)") (class "Default")
      (node (ref "ISOMETER_I/O") (pin "4") (pinfunction "4_4") (pintype "bidirectional"))
    )
    (net (code "54") (name "unconnected-(ISOMETER_I/O-Pad6)") (class "Default")
      (node (ref "ISOMETER_I/O") (pin "6") (pinfunction "6_6") (pintype "bidirectional"))
    )
    (net (code "55") (name "unconnected-(ISOMETER_I/O-Pad7)") (class "Default")
      (node (ref "ISOMETER_I/O") (pin "7") (pinfunction "7_7") (pintype "bidirectional"))
    )
    (net (code "56") (name "unconnected-(THERAL_EX_I/O-Pad7)") (class "Default")
      (node (ref "THERAL_EX_I/O") (pin "7") (pinfunction "7_7") (pintype "bidirectional"))
    )
    (net (code "57") (name "unconnected-(WIFI_I/O-Pad4)") (class "Default")
      (node (ref "WIFI_I/O") (pin "4") (pinfunction "4_4") (pintype "bidirectional"))
    )
    (net (code "58") (name "unconnected-(WIFI_I/O-Pad6)") (class "Default")
      (node (ref "WIFI_I/O") (pin "6") (pinfunction "6_6") (pintype "bidirectional"))
    )
    (net (code "59") (name "unconnected-(WIFI_I/O-Pad7)") (class "Default")
      (node (ref "WIFI_I/O") (pin "7") (pinfunction "7_7") (pintype "bidirectional"))
    )
    (net (code "60") (name "unconnected-(X1-Pad1)") (class "Default")
      (node (ref "X1") (pin "1") (pinfunction "1_1") (pintype "passive"))
    )
    (net (code "61") (name "unconnected-(X1-Pad2)") (class "Default")
      (node (ref "X1") (pin "2") (pinfunction "2_2") (pintype "passive"))
    )
    (net (code "62") (name "unconnected-(X1-Pad4)") (class "Default")
      (node (ref "X1") (pin "4") (pinfunction "4_4") (pintype "passive"))
    )
    (net (code "63") (name "unconnected-(X1-Pad6)") (class "Default")
      (node (ref "X1") (pin "6") (pinfunction "6_6") (pintype "passive"))
    )
    (net (code "64") (name "unconnected-(X1-Pad7)") (class "Default")
      (node (ref "X1") (pin "7") (pinfunction "7_7") (pintype "passive"))
    )
    (net (code "65") (name "unconnected-(X1-Pad8)") (class "Default")
      (node (ref "X1") (pin "8") (pinfunction "8_8") (pintype "passive"))
    )
    (net (code "66") (name "unconnected-(X1-Pad9)") (class "Default")
      (node (ref "X1") (pin "9") (pinfunction "9_9") (pintype "passive"))
    )
    (net (code "67") (name "unconnected-(X2-Pad1)") (class "Default")
      (node (ref "X2") (pin "1") (pinfunction "1_1") (pintype "passive"))
    )
    (net (code "68") (name "unconnected-(X2-Pad2)") (class "Default")
      (node (ref "X2") (pin "2") (pinfunction "2_2") (pintype "passive"))
    )
    (net (code "69") (name "unconnected-(X2-Pad4)") (class "Default")
      (node (ref "X2") (pin "4") (pinfunction "4_4") (pintype "passive"))
    )
    (net (code "70") (name "unconnected-(X2-Pad6)") (class "Default")
      (node (ref "X2") (pin "6") (pinfunction "6_6") (pintype "passive"))
    )
    (net (code "71") (name "unconnected-(X2-Pad7)") (class "Default")
      (node (ref "X2") (pin "7") (pinfunction "7_7") (pintype "passive"))
    )
    (net (code "72") (name "unconnected-(X2-Pad8)") (class "Default")
      (node (ref "X2") (pin "8") (pinfunction "8_8") (pintype "passive"))
    )
    (net (code "73") (name "unconnected-(X2-Pad9)") (class "Default")
      (node (ref "X2") (pin "9") (pinfunction "9_9") (pintype "passive"))
    )
  )
)
